# 3400.net
KiCad netlist of a schematic drawn in EAGLE
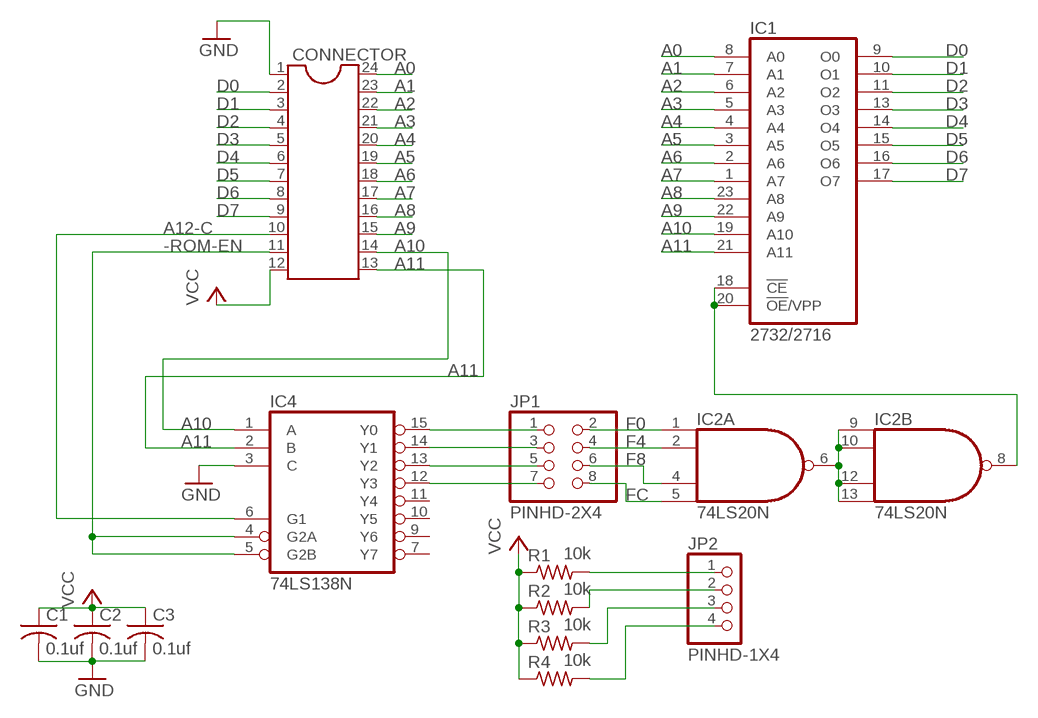
[diagram p0: schematic, sheet 1]

(export (version "E")
  (design (tool "Eeschema 10.0.6"))
  (components
    (comp (ref "C1")
      (value "0.1uf")
      (footprint "eagle-import:C025-024X044")
      (libsource (lib "eagle-import") (part "C-US025-024X044"))
    )
    (comp (ref "C2")
      (value "0.1uf")
      (footprint "eagle-import:C025-024X044")
      (libsource (lib "eagle-import") (part "C-US025-024X044"))
    )
    (comp (ref "C3")
      (value "0.1uf")
      (footprint "eagle-import:C025-024X044")
      (libsource (lib "eagle-import") (part "C-US025-024X044"))
    )
    (comp (ref "CONNECTOR")
      (value "DIL24-6")
      (footprint "eagle-import:DIL24-6")
      (libsource (lib "eagle-import") (part "DIL24-6"))
    )
    (comp (ref "IC1")
      (value "2732/2716")
      (footprint "eagle-import:DIL24")
      (libsource (lib "eagle-import") (part "2732"))
    )
    (comp (ref "IC2")
      (value "74LS20N")
      (footprint "eagle-import:DIL14")
      (libsource (lib "eagle-import") (part "7420NLS"))
    )
    (comp (ref "IC4")
      (value "74LS138N")
      (footprint "eagle-import:DIL16")
      (libsource (lib "eagle-import") (part "74138NLS"))
    )
    (comp (ref "JP1")
      (value "PINHD-2X4")
      (footprint "eagle-import:2X04")
      (libsource (lib "eagle-import") (part "PINHD-2X4"))
    )
    (comp (ref "JP2")
      (value "PINHD-1X4")
      (footprint "eagle-import:1X04")
      (libsource (lib "eagle-import") (part "PINHD-1X4"))
    )
    (comp (ref "R1")
      (value "10k")
      (footprint "eagle-import:0207_10")
      (libsource (lib "eagle-import") (part "R-US_0207/10"))
    )
    (comp (ref "R2")
      (value "10k")
      (footprint "eagle-import:0207_10")
      (libsource (lib "eagle-import") (part "R-US_0207/10"))
    )
    (comp (ref "R3")
      (value "10k")
      (footprint "eagle-import:0207_10")
      (libsource (lib "eagle-import") (part "R-US_0207/10"))
    )
    (comp (ref "R4")
      (value "10k")
      (footprint "eagle-import:0207_10")
      (libsource (lib "eagle-import") (part "R-US_0207/10"))
    )
  )
  (nets
    (net (code "1") (name "/-ROM-EN") (class "Default")
      (node (ref "CONNECTOR") (pin "11") (pinfunction "11_11") (pintype "passive"))
      (node (ref "IC4") (pin "4") (pinfunction "G2A_4") (pintype "input"))
      (node (ref "IC4") (pin "5") (pinfunction "G2B_5") (pintype "input"))
    )
    (net (code "2") (name "/A0") (class "Default")
      (node (ref "CONNECTOR") (pin "24") (pinfunction "24_24") (pintype "passive"))
      (node (ref "IC1") (pin "8") (pinfunction "A0_8") (pintype "input"))
    )
    (net (code "3") (name "/A1") (class "Default")
      (node (ref "CONNECTOR") (pin "23") (pinfunction "23_23") (pintype "passive"))
      (node (ref "IC1") (pin "7") (pinfunction "A1_7") (pintype "input"))
    )
    (net (code "4") (name "/A2") (class "Default")
      (node (ref "CONNECTOR") (pin "22") (pinfunction "22_22") (pintype "passive"))
      (node (ref "IC1") (pin "6") (pinfunction "A2_6") (pintype "input"))
    )
    (net (code "5") (name "/A3") (class "Default")
      (node (ref "CONNECTOR") (pin "21") (pinfunction "21_21") (pintype "passive"))
      (node (ref "IC1") (pin "5") (pinfunction "A3_5") (pintype "input"))
    )
    (net (code "6") (name "/A4") (class "Default")
      (node (ref "CONNECTOR") (pin "20") (pinfunction "20_20") (pintype "passive"))
      (node (ref "IC1") (pin "4") (pinfunction "A4_4") (pintype "input"))
    )
    (net (code "7") (name "/A5") (class "Default")
      (node (ref "CONNECTOR") (pin "19") (pinfunction "19_19") (pintype "passive"))
      (node (ref "IC1") (pin "3") (pinfunction "A5_3") (pintype "input"))
    )
    (net (code "8") (name "/A6") (class "Default")
      (node (ref "CONNECTOR") (pin "18") (pinfunction "18_18") (pintype "passive"))
      (node (ref "IC1") (pin "2") (pinfunction "A6_2") (pintype "input"))
    )
    (net (code "9") (name "/A7") (class "Default")
      (node (ref "CONNECTOR") (pin "17") (pinfunction "17_17") (pintype "passive"))
      (node (ref "IC1") (pin "1") (pinfunction "A7_1") (pintype "input"))
    )
    (net (code "10") (name "/A8") (class "Default")
      (node (ref "CONNECTOR") (pin "16") (pinfunction "16_16") (pintype "passive"))
      (node (ref "IC1") (pin "23") (pinfunction "A8_23") (pintype "input"))
    )
    (net (code "11") (name "/A9") (class "Default")
      (node (ref "CONNECTOR") (pin "15") (pinfunction "15_15") (pintype "passive"))
      (node (ref "IC1") (pin "22") (pinfunction "A9_22") (pintype "input"))
    )
    (net (code "12") (name "/A10") (class "Default")
      (node (ref "CONNECTOR") (pin "14") (pinfunction "14_14") (pintype "passive"))
      (node (ref "IC1") (pin "19") (pinfunction "A10_19") (pintype "input"))
      (node (ref "IC4") (pin "1") (pinfunction "A_1") (pintype "input"))
    )
    (net (code "13") (name "/A11") (class "Default")
      (node (ref "CONNECTOR") (pin "13") (pinfunction "13_13") (pintype "passive"))
      (node (ref "IC1") (pin "21") (pinfunction "A11_21") (pintype "input"))
      (node (ref "IC4") (pin "2") (pinfunction "B_2") (pintype "input"))
    )
    (net (code "14") (name "/A12-C") (class "Default")
      (node (ref "CONNECTOR") (pin "10") (pinfunction "10_10") (pintype "passive"))
      (node (ref "IC4") (pin "6") (pinfunction "G1_6") (pintype "input"))
    )
    (net (code "15") (name "/D0") (class "Default")
      (node (ref "CONNECTOR") (pin "2") (pinfunction "2_2") (pintype "passive"))
      (node (ref "IC1") (pin "9") (pinfunction "O0_9") (pintype "tri_state"))
    )
    (net (code "16") (name "/D1") (class "Default")
      (node (ref "CONNECTOR") (pin "3") (pinfunction "3_3") (pintype "passive"))
      (node (ref "IC1") (pin "10") (pinfunction "O1_10") (pintype "tri_state"))
    )
    (net (code "17") (name "/D2") (class "Default")
      (node (ref "CONNECTOR") (pin "4") (pinfunction "4_4") (pintype "passive"))
      (node (ref "IC1") (pin "11") (pinfunction "O2_11") (pintype "tri_state"))
    )
    (net (code "18") (name "/D3") (class "Default")
      (node (ref "CONNECTOR") (pin "5") (pinfunction "5_5") (pintype "passive"))
      (node (ref "IC1") (pin "13") (pinfunction "O3_13") (pintype "tri_state"))
    )
    (net (code "19") (name "/D4") (class "Default")
      (node (ref "CONNECTOR") (pin "6") (pinfunction "6_6") (pintype "passive"))
      (node (ref "IC1") (pin "14") (pinfunction "O4_14") (pintype "tri_state"))
    )
    (net (code "20") (name "/D5") (class "Default")
      (node (ref "CONNECTOR") (pin "7") (pinfunction "7_7") (pintype "passive"))
      (node (ref "IC1") (pin "15") (pinfunction "O5_15") (pintype "tri_state"))
    )
    (net (code "21") (name "/D6") (class "Default")
      (node (ref "CONNECTOR") (pin "8") (pinfunction "8_8") (pintype "passive"))
      (node (ref "IC1") (pin "16") (pinfunction "O6_16") (pintype "tri_state"))
    )
    (net (code "22") (name "/D7") (class "Default")
      (node (ref "CONNECTOR") (pin "9") (pinfunction "9_9") (pintype "passive"))
      (node (ref "IC1") (pin "17") (pinfunction "O7_17") (pintype "tri_state"))
    )
    (net (code "23") (name "/F0") (class "Default")
      (node (ref "IC2") (pin "1") (pinfunction "I0_1") (pintype "input"))
      (node (ref "JP1") (pin "2") (pinfunction "2_2") (pintype "passive"))
    )
    (net (code "24") (name "/F4") (class "Default")
      (node (ref "IC2") (pin "2") (pinfunction "I1_2") (pintype "input"))
      (node (ref "JP1") (pin "4") (pinfunction "4_4") (pintype "passive"))
    )
    (net (code "25") (name "/F8") (class "Default")
      (node (ref "IC2") (pin "4") (pinfunction "I2_4") (pintype "input"))
      (node (ref "JP1") (pin "6") (pinfunction "6_6") (pintype "passive"))
    )
    (net (code "26") (name "/FC") (class "Default")
      (node (ref "IC2") (pin "5") (pinfunction "I3_5") (pintype "input"))
      (node (ref "JP1") (pin "8") (pinfunction "8_8") (pintype "passive"))
    )
    (net (code "27") (name "GND") (class "Default")
      (node (ref "C1") (pin "2") (pinfunction "2_2") (pintype "passive"))
      (node (ref "C2") (pin "2") (pinfunction "2_2") (pintype "passive"))
      (node (ref "C3") (pin "2") (pinfunction "2_2") (pintype "passive"))
      (node (ref "CONNECTOR") (pin "1") (pinfunction "1_1") (pintype "passive"))
      (node (ref "IC4") (pin "3") (pinfunction "C_3") (pintype "input"))
    )
    (net (code "28") (name "Net-(IC1A-~{CE})") (class "Default")
      (node (ref "IC1") (pin "18") (pinfunction "~{CE}_18") (pintype "input"))
      (node (ref "IC1") (pin "20") (pinfunction "~{OE}/VPP_20") (pintype "input"))
      (node (ref "IC2") (pin "8") (pinfunction "O_8") (pintype "output"))
    )
    (net (code "29") (name "Net-(IC2A-O)") (class "Default")
      (node (ref "IC2") (pin "10") (pinfunction "I1_10") (pintype "input"))
      (node (ref "IC2") (pin "12") (pinfunction "I2_12") (pintype "input"))
      (node (ref "IC2") (pin "13") (pinfunction "I3_13") (pintype "input"))
      (node (ref "IC2") (pin "6") (pinfunction "O_6") (pintype "output"))
      (node (ref "IC2") (pin "9") (pinfunction "I0_9") (pintype "input"))
    )
    (net (code "30") (name "Net-(IC4A-Y0)") (class "Default")
      (node (ref "IC4") (pin "15") (pinfunction "Y0_15") (pintype "output"))
      (node (ref "JP1") (pin "1") (pinfunction "1_1") (pintype "passive"))
    )
    (net (code "31") (name "Net-(IC4A-Y1)") (class "Default")
      (node (ref "IC4") (pin "14") (pinfunction "Y1_14") (pintype "output"))
      (node (ref "JP1") (pin "3") (pinfunction "3_3") (pintype "passive"))
    )
    (net (code "32") (name "Net-(IC4A-Y2)") (class "Default")
      (node (ref "IC4") (pin "13") (pinfunction "Y2_13") (pintype "output"))
      (node (ref "JP1") (pin "5") (pinfunction "5_5") (pintype "passive"))
    )
    (net (code "33") (name "Net-(IC4A-Y3)") (class "Default")
      (node (ref "IC4") (pin "12") (pinfunction "Y3_12") (pintype "output"))
      (node (ref "JP1") (pin "7") (pinfunction "7_7") (pintype "passive"))
    )
    (net (code "34") (name "Net-(JP2-Pad1)") (class "Default")
      (node (ref "JP2") (pin "1") (pinfunction "1_1") (pintype "passive"))
      (node (ref "R1") (pin "2") (pinfunction "2_2") (pintype "passive"))
    )
    (net (code "35") (name "Net-(JP2-Pad2)") (class "Default")
      (node (ref "JP2") (pin "2") (pinfunction "2_2") (pintype "passive"))
      (node (ref "R2") (pin "2") (pinfunction "2_2") (pintype "passive"))
    )
    (net (code "36") (name "Net-(JP2-Pad3)") (class "Default")
      (node (ref "JP2") (pin "3") (pinfunction "3_3") (pintype "passive"))
      (node (ref "R3") (pin "2") (pinfunction "2_2") (pintype "passive"))
    )
    (net (code "37") (name "Net-(JP2-Pad4)") (class "Default")
      (node (ref "JP2") (pin "4") (pinfunction "4_4") (pintype "passive"))
      (node (ref "R4") (pin "2") (pinfunction "2_2") (pintype "passive"))
    )
    (net (code "38") (name "VCC") (class "Default")
      (node (ref "C1") (pin "1") (pinfunction "1_1") (pintype "passive"))
      (node (ref "C2") (pin "1") (pinfunction "1_1") (pintype "passive"))
      (node (ref "C3") (pin "1") (pinfunction "1_1") (pintype "passive"))
      (node (ref "CONNECTOR") (pin "12") (pinfunction "12_12") (pintype "passive"))
      (node (ref "R1") (pin "1") (pinfunction "1_1") (pintype "passive"))
      (node (ref "R2") (pin "1") (pinfunction "1_1") (pintype "passive"))
      (node (ref "R3") (pin "1") (pinfunction "1_1") (pintype "passive"))
      (node (ref "R4") (pin "1") (pinfunction "1_1") (pintype "passive"))
    )
    (net (code "39") (name "unconnected-(IC4A-Y4-Pad11)") (class "Default")
      (node (ref "IC4") (pin "11") (pinfunction "Y4_11") (pintype "output"))
    )
    (net (code "40") (name "unconnected-(IC4A-Y5-Pad10)") (class "Default")
      (node (ref "IC4") (pin "10") (pinfunction "Y5_10") (pintype "output"))
    )
    (net (code "41") (name "unconnected-(IC4A-Y6-Pad9)") (class "Default")
      (node (ref "IC4") (pin "9") (pinfunction "Y6_9") (pintype "output"))
    )
    (net (code "42") (name "unconnected-(IC4A-Y7-Pad7)") (class "Default")
      (node (ref "IC4") (pin "7") (pinfunction "Y7_7") (pintype "output"))
    )
  )
)
